# atmega48A_dip_jumpers.net
KiCad netlist of a schematic drawn in EAGLE
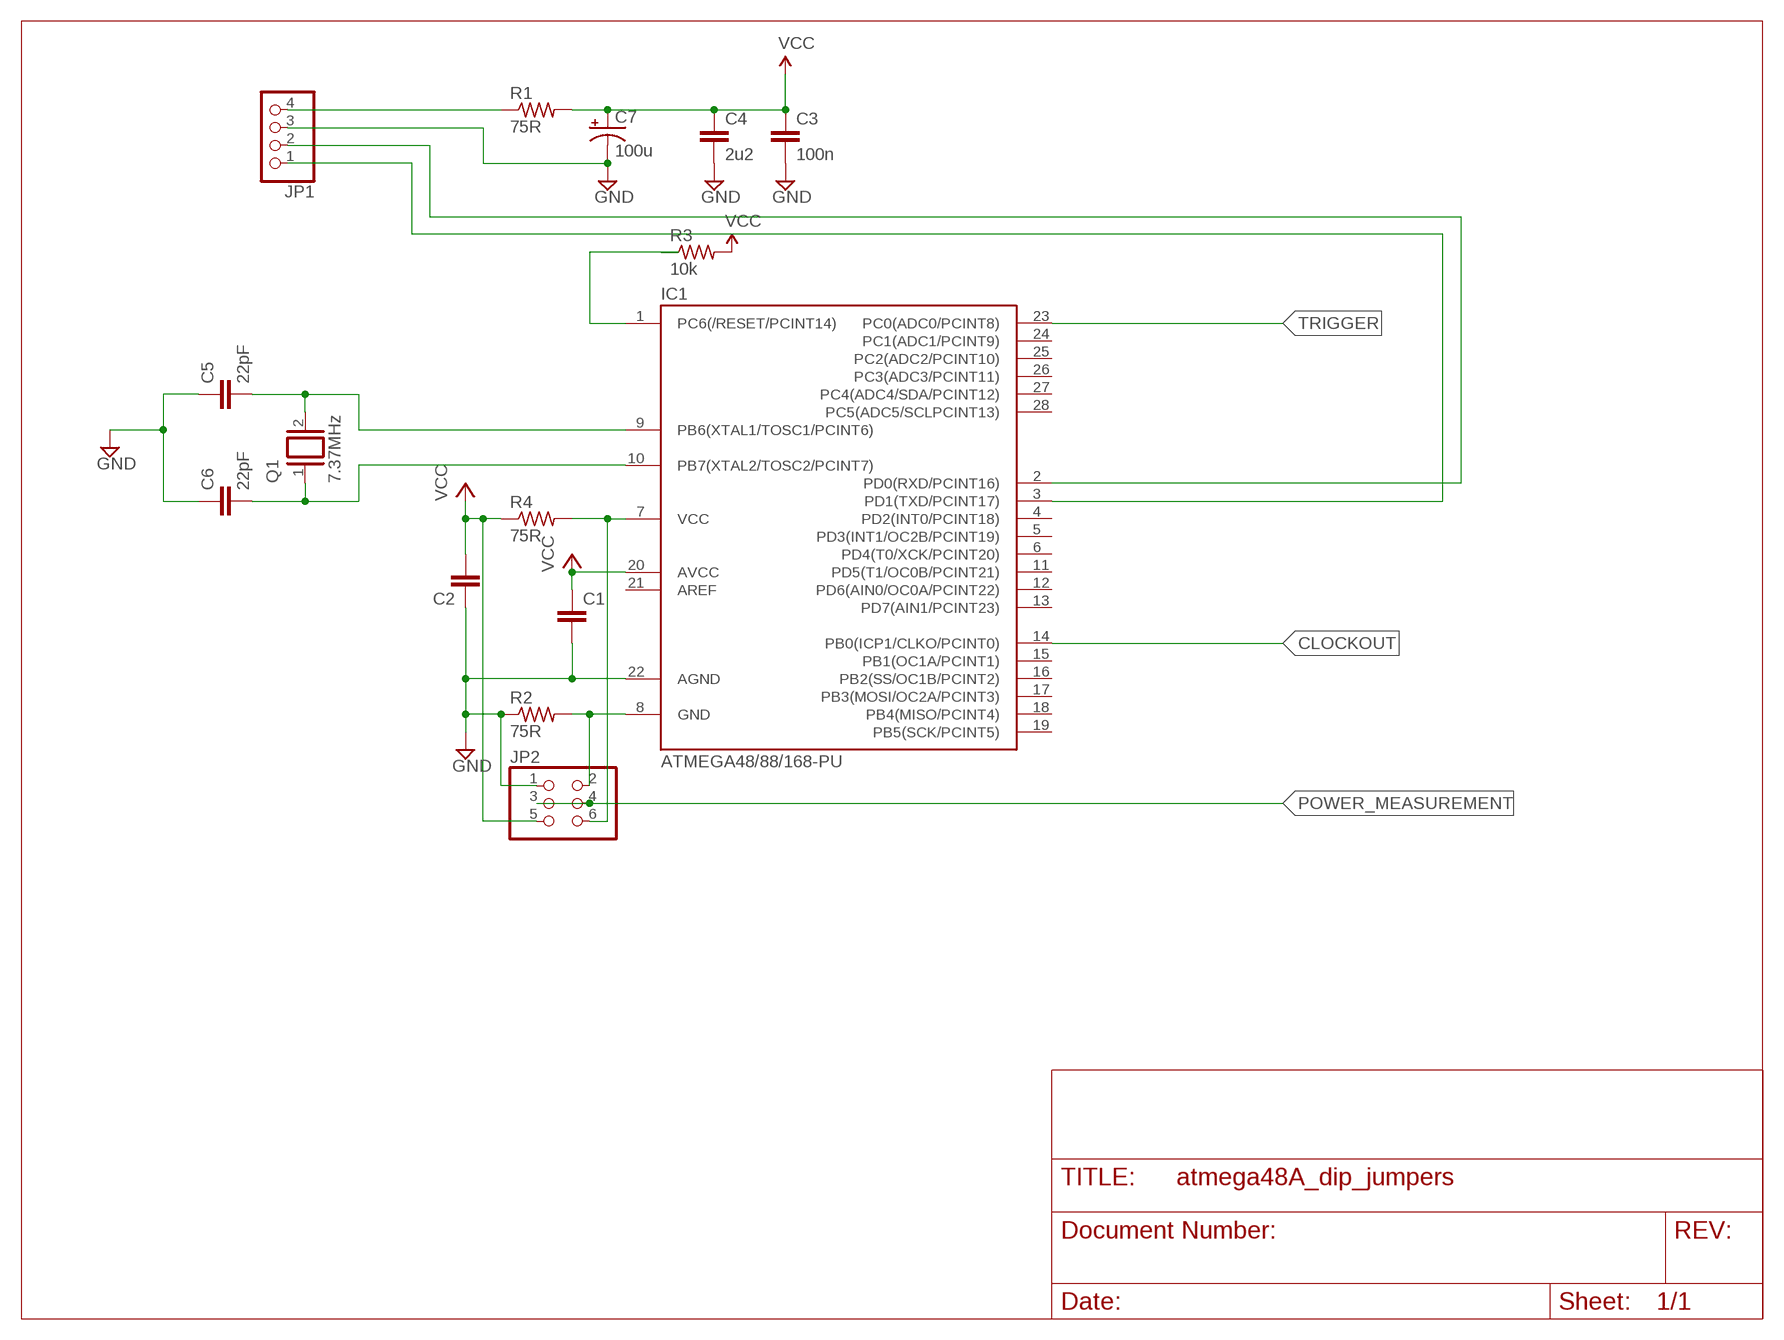
[diagram p0: schematic, sheet 1]

(export (version "E")
  (design (tool "Eeschema 10.0.6"))
  (components
    (comp (ref "C1")
      (value "C-EUC0805")
      (footprint "eagle-import:C0805")
      (libsource (lib "eagle-import") (part "C-EUC0805"))
    )
    (comp (ref "C2")
      (value "C-EUC0805")
      (footprint "eagle-import:C0805")
      (libsource (lib "eagle-import") (part "C-EUC0805"))
    )
    (comp (ref "C3")
      (value "100n")
      (footprint "eagle-import:C0805")
      (libsource (lib "eagle-import") (part "C-EUC0805"))
    )
    (comp (ref "C4")
      (value "2u2")
      (footprint "eagle-import:C0805")
      (libsource (lib "eagle-import") (part "C-EUC0805"))
    )
    (comp (ref "C5")
      (value "22pF")
      (footprint "eagle-import:C0805")
      (libsource (lib "eagle-import") (part "C-EUC0805"))
    )
    (comp (ref "C6")
      (value "22pF")
      (footprint "eagle-import:C0805")
      (libsource (lib "eagle-import") (part "C-EUC0805"))
    )
    (comp (ref "C7")
      (value "100u")
      (footprint "eagle-import:140CLH-0810")
      (libsource (lib "eagle-import") (part "CPOL-US140CLH-0810"))
    )
    (comp (ref "IC1")
      (value "ATMEGA48/88/168-PU")
      (footprint "eagle-import:DIL28-3")
      (libsource (lib "eagle-import") (part "ATMEGA48/88/168-PU"))
    )
    (comp (ref "JP1")
      (value "PINHD-1X4/90")
      (footprint "eagle-import:1X04_90")
      (libsource (lib "eagle-import") (part "PINHD-1X4/90"))
    )
    (comp (ref "JP2")
      (value "PINHD-2X3")
      (footprint "eagle-import:2X03")
      (libsource (lib "eagle-import") (part "PINHD-2X3"))
    )
    (comp (ref "Q1")
      (value "7.37MHz")
      (footprint "eagle-import:Q")
      (libsource (lib "eagle-import") (part "XTAL"))
    )
    (comp (ref "R1")
      (value "75R")
      (footprint "eagle-import:M0805")
      (libsource (lib "eagle-import") (part "R-US_M0805"))
    )
    (comp (ref "R2")
      (value "75R")
      (footprint "eagle-import:R0805")
      (libsource (lib "eagle-import") (part "resistor_R-US_R0805"))
    )
    (comp (ref "R3")
      (value "10k")
      (footprint "eagle-import:M0805")
      (libsource (lib "eagle-import") (part "R-US_M0805"))
    )
    (comp (ref "R4")
      (value "75R")
      (footprint "eagle-import:R0805")
      (libsource (lib "eagle-import") (part "resistor_R-US_R0805"))
    )
  )
  (nets
    (net (code "1") (name "CLOCKOUT") (class "Default")
      (node (ref "IC1") (pin "14") (pinfunction "PB0(ICP1/CLKO/PCINT0)_14") (pintype "bidirectional"))
    )
    (net (code "2") (name "GND") (class "Default")
      (node (ref "C1") (pin "2") (pinfunction "2_2") (pintype "passive"))
      (node (ref "C2") (pin "1") (pinfunction "1_1") (pintype "passive"))
      (node (ref "C3") (pin "2") (pinfunction "2_2") (pintype "passive"))
      (node (ref "C4") (pin "2") (pinfunction "2_2") (pintype "passive"))
      (node (ref "C5") (pin "1") (pinfunction "1_1") (pintype "passive"))
      (node (ref "C6") (pin "1") (pinfunction "1_1") (pintype "passive"))
      (node (ref "C7") (pin "-") (pinfunction "-_-") (pintype "passive"))
      (node (ref "IC1") (pin "22") (pinfunction "AGND_22") (pintype "power_in"))
      (node (ref "JP1") (pin "3") (pinfunction "3_3") (pintype "passive"))
      (node (ref "JP2") (pin "1") (pinfunction "1_1") (pintype "passive"))
      (node (ref "R2") (pin "1") (pinfunction "1_1") (pintype "passive"))
    )
    (net (code "3") (name "Net-(IC1-GND)") (class "Default")
      (node (ref "IC1") (pin "8") (pinfunction "GND_8") (pintype "power_in"))
      (node (ref "JP2") (pin "2") (pinfunction "2_2") (pintype "passive"))
      (node (ref "R2") (pin "2") (pinfunction "2_2") (pintype "passive"))
    )
    (net (code "4") (name "Net-(IC1-PB6(XTAL1{slash}TOSC1{slash}PCINT6))") (class "Default")
      (node (ref "C5") (pin "2") (pinfunction "2_2") (pintype "passive"))
      (node (ref "IC1") (pin "9") (pinfunction "PB6(XTAL1/TOSC1/PCINT6)_9") (pintype "bidirectional"))
      (node (ref "Q1") (pin "2") (pinfunction "2_2") (pintype "passive"))
    )
    (net (code "5") (name "Net-(IC1-PB7(XTAL2{slash}TOSC2{slash}PCINT7))") (class "Default")
      (node (ref "C6") (pin "2") (pinfunction "2_2") (pintype "passive"))
      (node (ref "IC1") (pin "10") (pinfunction "PB7(XTAL2/TOSC2/PCINT7)_10") (pintype "bidirectional"))
      (node (ref "Q1") (pin "1") (pinfunction "1_1") (pintype "passive"))
    )
    (net (code "6") (name "Net-(IC1-PD0(RXD{slash}PCINT16))") (class "Default")
      (node (ref "IC1") (pin "2") (pinfunction "PD0(RXD/PCINT16)_2") (pintype "bidirectional"))
      (node (ref "JP1") (pin "2") (pinfunction "2_2") (pintype "passive"))
    )
    (net (code "7") (name "Net-(IC1-PD1(TXD{slash}PCINT17))") (class "Default")
      (node (ref "IC1") (pin "3") (pinfunction "PD1(TXD/PCINT17)_3") (pintype "bidirectional"))
      (node (ref "JP1") (pin "1") (pinfunction "1_1") (pintype "passive"))
    )
    (net (code "8") (name "Net-(IC1-VCC)") (class "Default")
      (node (ref "IC1") (pin "7") (pinfunction "VCC_7") (pintype "power_in"))
      (node (ref "JP2") (pin "6") (pinfunction "6_6") (pintype "passive"))
      (node (ref "R4") (pin "2") (pinfunction "2_2") (pintype "passive"))
    )
    (net (code "9") (name "Net-(JP1-Pad4)") (class "Default")
      (node (ref "JP1") (pin "4") (pinfunction "4_4") (pintype "passive"))
      (node (ref "R1") (pin "1") (pinfunction "1_1") (pintype "passive"))
    )
    (net (code "10") (name "POWER_MEASUREMENT") (class "Default")
      (node (ref "JP2") (pin "3") (pinfunction "3_3") (pintype "passive"))
      (node (ref "JP2") (pin "4") (pinfunction "4_4") (pintype "passive"))
    )
    (net (code "11") (name "TRIGGER") (class "Default")
      (node (ref "IC1") (pin "23") (pinfunction "PC0(ADC0/PCINT8)_23") (pintype "bidirectional"))
    )
    (net (code "12") (name "VCC") (class "Default")
      (node (ref "C1") (pin "1") (pinfunction "1_1") (pintype "passive"))
      (node (ref "C2") (pin "2") (pinfunction "2_2") (pintype "passive"))
      (node (ref "C3") (pin "1") (pinfunction "1_1") (pintype "passive"))
      (node (ref "C4") (pin "1") (pinfunction "1_1") (pintype "passive"))
      (node (ref "C7") (pin "+") (pinfunction "+_+") (pintype "passive"))
      (node (ref "IC1") (pin "20") (pinfunction "AVCC_20") (pintype "passive"))
      (node (ref "JP2") (pin "5") (pinfunction "5_5") (pintype "passive"))
      (node (ref "R1") (pin "2") (pinfunction "2_2") (pintype "passive"))
      (node (ref "R3") (pin "2") (pinfunction "2_2") (pintype "passive"))
      (node (ref "R4") (pin "1") (pinfunction "1_1") (pintype "passive"))
    )
    (net (code "13") (name "unconnected-(IC1-AREF-Pad21)") (class "Default")
      (node (ref "IC1") (pin "21") (pinfunction "AREF_21") (pintype "passive"))
    )
    (net (code "14") (name "unconnected-(IC1-PB1(OC1A{slash}PCINT1)-Pad15)") (class "Default")
      (node (ref "IC1") (pin "15") (pinfunction "PB1(OC1A/PCINT1)_15") (pintype "bidirectional"))
    )
    (net (code "15") (name "unconnected-(IC1-PB2(SS{slash}OC1B{slash}PCINT2)-Pad16)") (class "Default")
      (node (ref "IC1") (pin "16") (pinfunction "PB2(SS/OC1B/PCINT2)_16") (pintype "bidirectional"))
    )
    (net (code "16") (name "unconnected-(IC1-PB3(MOSI{slash}OC2A{slash}PCINT3)-Pad17)") (class "Default")
      (node (ref "IC1") (pin "17") (pinfunction "PB3(MOSI/OC2A/PCINT3)_17") (pintype "bidirectional"))
    )
    (net (code "17") (name "unconnected-(IC1-PB4(MISO{slash}PCINT4)-Pad18)") (class "Default")
      (node (ref "IC1") (pin "18") (pinfunction "PB4(MISO/PCINT4)_18") (pintype "bidirectional"))
    )
    (net (code "18") (name "unconnected-(IC1-PB5(SCK{slash}PCINT5)-Pad19)") (class "Default")
      (node (ref "IC1") (pin "19") (pinfunction "PB5(SCK/PCINT5)_19") (pintype "bidirectional"))
    )
    (net (code "19") (name "unconnected-(IC1-PC1(ADC1{slash}PCINT9)-Pad24)") (class "Default")
      (node (ref "IC1") (pin "24") (pinfunction "PC1(ADC1/PCINT9)_24") (pintype "bidirectional"))
    )
    (net (code "20") (name "unconnected-(IC1-PC2(ADC2{slash}PCINT10)-Pad25)") (class "Default")
      (node (ref "IC1") (pin "25") (pinfunction "PC2(ADC2/PCINT10)_25") (pintype "bidirectional"))
    )
    (net (code "21") (name "unconnected-(IC1-PC3(ADC3{slash}PCINT11)-Pad26)") (class "Default")
      (node (ref "IC1") (pin "26") (pinfunction "PC3(ADC3/PCINT11)_26") (pintype "bidirectional"))
    )
    (net (code "22") (name "unconnected-(IC1-PC4(ADC4{slash}SDA{slash}PCINT12)-Pad27)") (class "Default")
      (node (ref "IC1") (pin "27") (pinfunction "PC4(ADC4/SDA/PCINT12)_27") (pintype "bidirectional"))
    )
    (net (code "23") (name "unconnected-(IC1-PC5(ADC5{slash}SCLPCINT13)-Pad28)") (class "Default")
      (node (ref "IC1") (pin "28") (pinfunction "PC5(ADC5/SCLPCINT13)_28") (pintype "bidirectional"))
    )
    (net (code "24") (name "unconnected-(IC1-PC6({slash}RESET{slash}PCINT14)-Pad1)") (class "Default")
      (node (ref "IC1") (pin "1") (pinfunction "PC6(/RESET/PCINT14)_1") (pintype "bidirectional"))
    )
    (net (code "25") (name "unconnected-(IC1-PD2(INT0{slash}PCINT18)-Pad4)") (class "Default")
      (node (ref "IC1") (pin "4") (pinfunction "PD2(INT0/PCINT18)_4") (pintype "bidirectional"))
    )
    (net (code "26") (name "unconnected-(IC1-PD3(INT1{slash}OC2B{slash}PCINT19)-Pad5)") (class "Default")
      (node (ref "IC1") (pin "5") (pinfunction "PD3(INT1/OC2B/PCINT19)_5") (pintype "bidirectional"))
    )
    (net (code "27") (name "unconnected-(IC1-PD4(T0{slash}XCK{slash}PCINT20)-Pad6)") (class "Default")
      (node (ref "IC1") (pin "6") (pinfunction "PD4(T0/XCK/PCINT20)_6") (pintype "bidirectional"))
    )
    (net (code "28") (name "unconnected-(IC1-PD5(T1{slash}OC0B{slash}PCINT21)-Pad11)") (class "Default")
      (node (ref "IC1") (pin "11") (pinfunction "PD5(T1/OC0B/PCINT21)_11") (pintype "bidirectional"))
    )
    (net (code "29") (name "unconnected-(IC1-PD6(AIN0{slash}OC0A{slash}PCINT22)-Pad12)") (class "Default")
      (node (ref "IC1") (pin "12") (pinfunction "PD6(AIN0/OC0A/PCINT22)_12") (pintype "bidirectional"))
    )
    (net (code "30") (name "unconnected-(IC1-PD7(AIN1{slash}PCINT23)-Pad13)") (class "Default")
      (node (ref "IC1") (pin "13") (pinfunction "PD7(AIN1/PCINT23)_13") (pintype "bidirectional"))
    )
    (net (code "31") (name "unconnected-(R3-Pad1)") (class "Default")
      (node (ref "R3") (pin "1") (pinfunction "1_1") (pintype "passive"))
    )
  )
)
